# 12_IO_PORT.net
KiCad netlist of a schematic drawn in Altium Designer
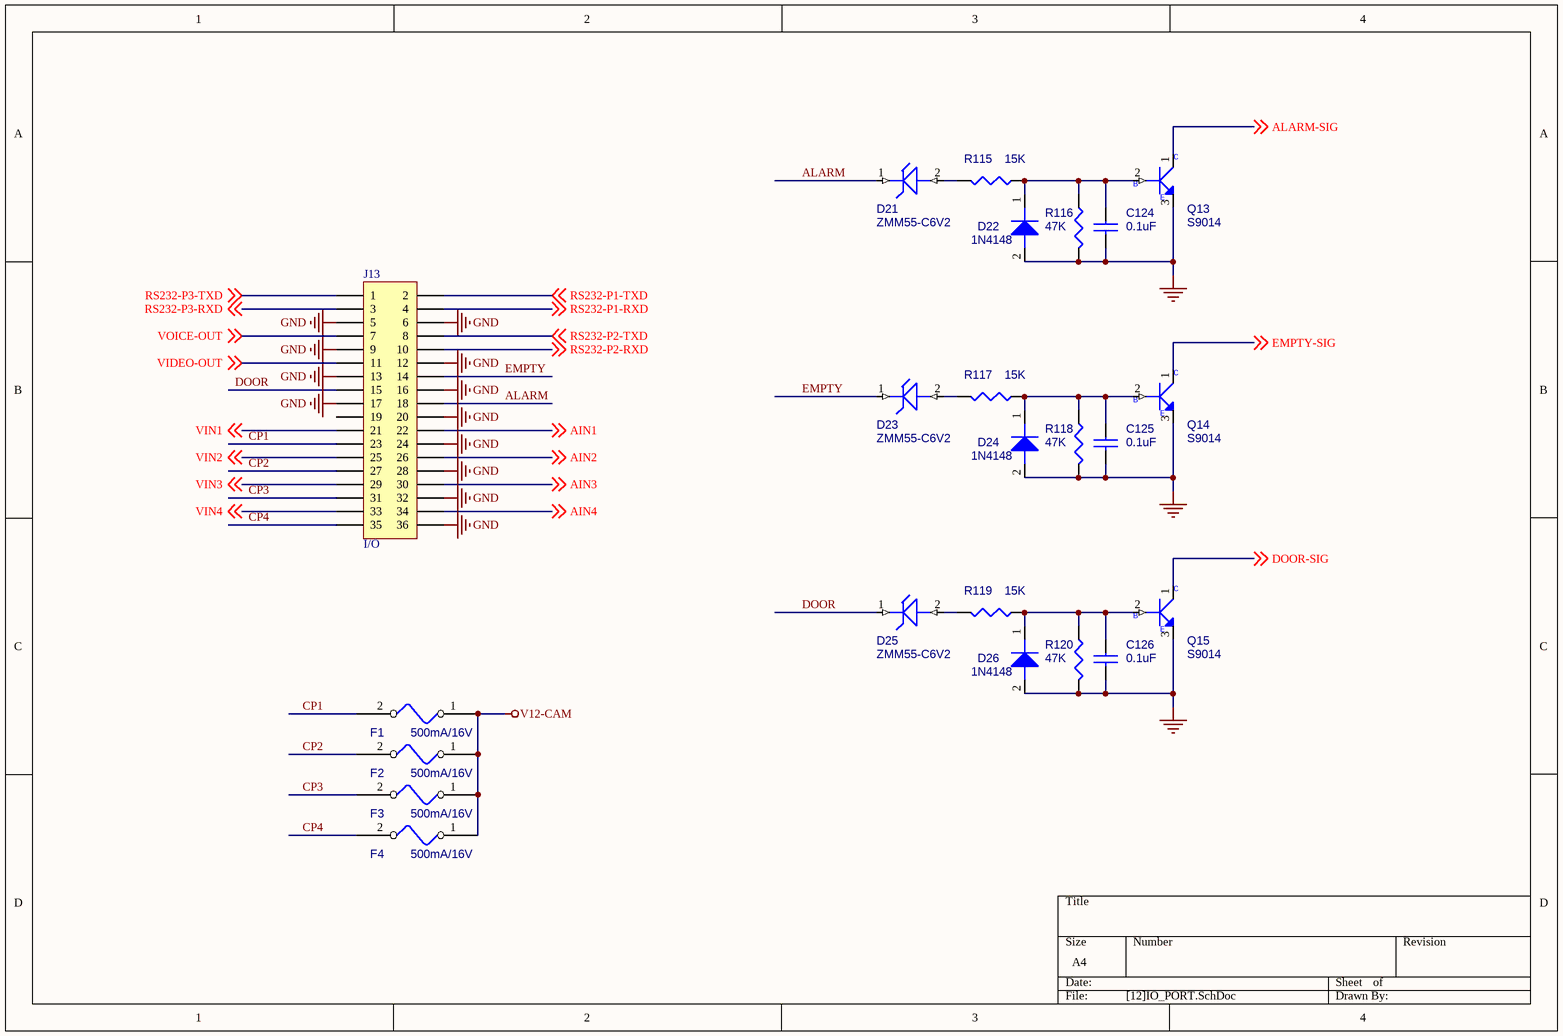
[diagram p0: [12]IO_PORT.SchDoc]

(export (version "E")
  (design (tool "Eeschema 10.0.6"))
  (components
    (comp (ref "C124") (value "0.1uF") (libsource (lib "*") (part "CAP")))
    (comp (ref "C125") (value "0.1uF") (libsource (lib "*") (part "CAP")))
    (comp (ref "C126") (value "0.1uF") (libsource (lib "*") (part "CAP")))
    (comp (ref "D21")
      (value "ZMM55-C6V2")
      (footprint "MINI-MELF")
      (libsource (lib "*") (part "MMGZ5231BPTLL34"))
    )
    (comp (ref "D22")
      (value "1N4148")
      (footprint "MINI-MELF")
      (libsource (lib "*") (part "1N4148WS-7-F_SOD323-2"))
    )
    (comp (ref "D23")
      (value "ZMM55-C6V2")
      (footprint "MINI-MELF")
      (libsource (lib "*") (part "MMGZ5231BPTLL34"))
    )
    (comp (ref "D24")
      (value "1N4148")
      (footprint "MINI-MELF")
      (libsource (lib "*") (part "1N4148WS-7-F_SOD323-2"))
    )
    (comp (ref "D25")
      (value "ZMM55-C6V2")
      (footprint "MINI-MELF")
      (libsource (lib "*") (part "MMGZ5231BPTLL34"))
    )
    (comp (ref "D26")
      (value "1N4148")
      (footprint "MINI-MELF")
      (libsource (lib "*") (part "1N4148WS-7-F_SOD323-2"))
    )
    (comp (ref "F1") (value "500mA/16V") (libsource (lib "*") (part "2A_32VDC_0467-002")))
    (comp (ref "F2") (value "500mA/16V") (libsource (lib "*") (part "2A_32VDC_0467-002")))
    (comp (ref "F3") (value "500mA/16V") (libsource (lib "*") (part "2A_32VDC_0467-002")))
    (comp (ref "F4") (value "500mA/16V") (libsource (lib "*") (part "2A_32VDC_0467-002")))
    (comp (ref "J13")
      (value "I/O")
      (footprint "AMP174146")
      (description "Header, 18-Pin, Dual row, Right Angle")
      (fields (field (name "PUBLISHER") "Altium Limited"))
      (libsource (lib "Miscellaneous Connectors") (part "Header 18X2H"))
    )
    (comp (ref "Q13")
      (value "S9014")
      (footprint "NPN")
      (fields (field (name "PART NUMBER") "SB039040000"))
      (libsource (lib "*") (part "MMBT3904_NL_SOT23-3"))
    )
    (comp (ref "Q14")
      (value "S9014")
      (footprint "NPN")
      (fields (field (name "PART NUMBER") "SB039040000"))
      (libsource (lib "*") (part "MMBT3904_NL_SOT23-3"))
    )
    (comp (ref "Q15")
      (value "S9014")
      (footprint "NPN")
      (fields (field (name "PART NUMBER") "SB039040000"))
      (libsource (lib "*") (part "MMBT3904_NL_SOT23-3"))
    )
    (comp (ref "R115") (value "15K") (libsource (lib "*") (part "R")))
    (comp (ref "R116") (value "47K") (libsource (lib "*") (part "R")))
    (comp (ref "R117") (value "15K") (libsource (lib "*") (part "R")))
    (comp (ref "R118") (value "47K") (libsource (lib "*") (part "R")))
    (comp (ref "R119") (value "15K") (libsource (lib "*") (part "R")))
    (comp (ref "R120") (value "47K") (libsource (lib "*") (part "R")))
  )
  (nets
    (net (code "1") (name "/ALARM") (class "Default")
      (node (ref "D21") (pin "1") (pinfunction "1_1") (pintype "input"))
      (node (ref "J13") (pin "18") (pinfunction "18_18") (pintype "passive"))
    )
    (net (code "2") (name "/CP1") (class "Default")
      (node (ref "F1") (pin "2") (pinfunction "2_2") (pintype "passive"))
      (node (ref "J13") (pin "23") (pinfunction "23_23") (pintype "passive"))
    )
    (net (code "3") (name "/CP2") (class "Default")
      (node (ref "F2") (pin "2") (pinfunction "2_2") (pintype "passive"))
      (node (ref "J13") (pin "27") (pinfunction "27_27") (pintype "passive"))
    )
    (net (code "4") (name "/CP3") (class "Default")
      (node (ref "F3") (pin "2") (pinfunction "2_2") (pintype "passive"))
      (node (ref "J13") (pin "31") (pinfunction "31_31") (pintype "passive"))
    )
    (net (code "5") (name "/CP4") (class "Default")
      (node (ref "F4") (pin "2") (pinfunction "2_2") (pintype "passive"))
      (node (ref "J13") (pin "35") (pinfunction "35_35") (pintype "passive"))
    )
    (net (code "6") (name "/DOOR") (class "Default")
      (node (ref "D25") (pin "1") (pinfunction "1_1") (pintype "input"))
      (node (ref "J13") (pin "15") (pinfunction "15_15") (pintype "passive"))
    )
    (net (code "7") (name "/EMPTY") (class "Default")
      (node (ref "D23") (pin "1") (pinfunction "1_1") (pintype "input"))
      (node (ref "J13") (pin "14") (pinfunction "14_14") (pintype "passive"))
    )
    (net (code "8") (name "AIN1") (class "Default")
      (node (ref "J13") (pin "22") (pinfunction "22_22") (pintype "passive"))
    )
    (net (code "9") (name "AIN2") (class "Default")
      (node (ref "J13") (pin "26") (pinfunction "26_26") (pintype "passive"))
    )
    (net (code "10") (name "AIN3") (class "Default")
      (node (ref "J13") (pin "30") (pinfunction "30_30") (pintype "passive"))
    )
    (net (code "11") (name "AIN4") (class "Default")
      (node (ref "J13") (pin "34") (pinfunction "34_34") (pintype "passive"))
    )
    (net (code "12") (name "ALARM-SIG") (class "Default")
      (node (ref "Q13") (pin "1") (pinfunction "COLLECTOR_1") (pintype "passive"))
    )
    (net (code "13") (name "DOOR-SIG") (class "Default")
      (node (ref "Q15") (pin "1") (pinfunction "COLLECTOR_1") (pintype "passive"))
    )
    (net (code "14") (name "EMPTY-SIG") (class "Default")
      (node (ref "Q14") (pin "1") (pinfunction "COLLECTOR_1") (pintype "passive"))
    )
    (net (code "15") (name "GND") (class "Default")
      (node (ref "C124") (pin "2") (pinfunction "2_2") (pintype "passive"))
      (node (ref "C125") (pin "2") (pinfunction "2_2") (pintype "passive"))
      (node (ref "C126") (pin "2") (pinfunction "2_2") (pintype "passive"))
      (node (ref "D22") (pin "2") (pinfunction "2_2") (pintype "passive"))
      (node (ref "D24") (pin "2") (pinfunction "2_2") (pintype "passive"))
      (node (ref "D26") (pin "2") (pinfunction "2_2") (pintype "passive"))
      (node (ref "J13") (pin "12") (pinfunction "12_12") (pintype "passive"))
      (node (ref "J13") (pin "13") (pinfunction "13_13") (pintype "passive"))
      (node (ref "J13") (pin "16") (pinfunction "16_16") (pintype "passive"))
      (node (ref "J13") (pin "17") (pinfunction "17_17") (pintype "passive"))
      (node (ref "J13") (pin "20") (pinfunction "20_20") (pintype "passive"))
      (node (ref "J13") (pin "24") (pinfunction "24_24") (pintype "passive"))
      (node (ref "J13") (pin "28") (pinfunction "28_28") (pintype "passive"))
      (node (ref "J13") (pin "32") (pinfunction "32_32") (pintype "passive"))
      (node (ref "J13") (pin "36") (pinfunction "36_36") (pintype "passive"))
      (node (ref "J13") (pin "5") (pinfunction "5_5") (pintype "passive"))
      (node (ref "J13") (pin "6") (pinfunction "6_6") (pintype "passive"))
      (node (ref "J13") (pin "9") (pinfunction "9_9") (pintype "passive"))
      (node (ref "Q13") (pin "3") (pinfunction "EMITTER_3") (pintype "passive"))
      (node (ref "Q14") (pin "3") (pinfunction "EMITTER_3") (pintype "passive"))
      (node (ref "Q15") (pin "3") (pinfunction "EMITTER_3") (pintype "passive"))
      (node (ref "R116") (pin "2") (pinfunction "2_2") (pintype "passive"))
      (node (ref "R118") (pin "2") (pinfunction "2_2") (pintype "passive"))
      (node (ref "R120") (pin "2") (pinfunction "2_2") (pintype "passive"))
    )
    (net (code "16") (name "Net-(D21-Pad2)") (class "Default")
      (node (ref "D21") (pin "2") (pinfunction "2_2") (pintype "input"))
      (node (ref "R115") (pin "2") (pinfunction "2_2") (pintype "passive"))
    )
    (net (code "17") (name "Net-(D23-Pad2)") (class "Default")
      (node (ref "D23") (pin "2") (pinfunction "2_2") (pintype "input"))
      (node (ref "R117") (pin "2") (pinfunction "2_2") (pintype "passive"))
    )
    (net (code "18") (name "Net-(D25-Pad2)") (class "Default")
      (node (ref "D25") (pin "2") (pinfunction "2_2") (pintype "input"))
      (node (ref "R119") (pin "2") (pinfunction "2_2") (pintype "passive"))
    )
    (net (code "19") (name "Net-(Q13-BASE)") (class "Default")
      (node (ref "C124") (pin "1") (pinfunction "1_1") (pintype "passive"))
      (node (ref "D22") (pin "1") (pinfunction "1_1") (pintype "passive"))
      (node (ref "Q13") (pin "2") (pinfunction "BASE_2") (pintype "input"))
      (node (ref "R115") (pin "1") (pinfunction "1_1") (pintype "passive"))
      (node (ref "R116") (pin "1") (pinfunction "1_1") (pintype "passive"))
    )
    (net (code "20") (name "Net-(Q14-BASE)") (class "Default")
      (node (ref "C125") (pin "1") (pinfunction "1_1") (pintype "passive"))
      (node (ref "D24") (pin "1") (pinfunction "1_1") (pintype "passive"))
      (node (ref "Q14") (pin "2") (pinfunction "BASE_2") (pintype "input"))
      (node (ref "R117") (pin "1") (pinfunction "1_1") (pintype "passive"))
      (node (ref "R118") (pin "1") (pinfunction "1_1") (pintype "passive"))
    )
    (net (code "21") (name "Net-(Q15-BASE)") (class "Default")
      (node (ref "C126") (pin "1") (pinfunction "1_1") (pintype "passive"))
      (node (ref "D26") (pin "1") (pinfunction "1_1") (pintype "passive"))
      (node (ref "Q15") (pin "2") (pinfunction "BASE_2") (pintype "input"))
      (node (ref "R119") (pin "1") (pinfunction "1_1") (pintype "passive"))
      (node (ref "R120") (pin "1") (pinfunction "1_1") (pintype "passive"))
    )
    (net (code "22") (name "RS232-P1-RXD") (class "Default")
      (node (ref "J13") (pin "4") (pinfunction "4_4") (pintype "passive"))
    )
    (net (code "23") (name "RS232-P1-TXD") (class "Default")
      (node (ref "J13") (pin "2") (pinfunction "2_2") (pintype "passive"))
    )
    (net (code "24") (name "RS232-P2-RXD") (class "Default")
      (node (ref "J13") (pin "10") (pinfunction "10_10") (pintype "passive"))
    )
    (net (code "25") (name "RS232-P2-TXD") (class "Default")
      (node (ref "J13") (pin "8") (pinfunction "8_8") (pintype "passive"))
    )
    (net (code "26") (name "RS232-P3-RXD") (class "Default")
      (node (ref "J13") (pin "3") (pinfunction "3_3") (pintype "passive"))
    )
    (net (code "27") (name "RS232-P3-TXD") (class "Default")
      (node (ref "J13") (pin "1") (pinfunction "1_1") (pintype "passive"))
    )
    (net (code "28") (name "V12-CAM") (class "Default")
      (node (ref "F1") (pin "1") (pinfunction "1_1") (pintype "passive"))
      (node (ref "F2") (pin "1") (pinfunction "1_1") (pintype "passive"))
      (node (ref "F3") (pin "1") (pinfunction "1_1") (pintype "passive"))
      (node (ref "F4") (pin "1") (pinfunction "1_1") (pintype "passive"))
    )
    (net (code "29") (name "VIDEO-OUT") (class "Default")
      (node (ref "J13") (pin "11") (pinfunction "11_11") (pintype "passive"))
    )
    (net (code "30") (name "VIN1") (class "Default")
      (node (ref "J13") (pin "21") (pinfunction "21_21") (pintype "passive"))
    )
    (net (code "31") (name "VIN2") (class "Default")
      (node (ref "J13") (pin "25") (pinfunction "25_25") (pintype "passive"))
    )
    (net (code "32") (name "VIN3") (class "Default")
      (node (ref "J13") (pin "29") (pinfunction "29_29") (pintype "passive"))
    )
    (net (code "33") (name "VIN4") (class "Default")
      (node (ref "J13") (pin "33") (pinfunction "33_33") (pintype "passive"))
    )
    (net (code "34") (name "VOICE-OUT") (class "Default")
      (node (ref "J13") (pin "7") (pinfunction "7_7") (pintype "passive"))
    )
    (net (code "35") (name "unconnected-(J13-Pad19)") (class "Default")
      (node (ref "J13") (pin "19") (pinfunction "19_19") (pintype "passive"))
    )
  )
)
